# 16-Power.net
KiCad netlist of a schematic drawn in Altium Designer
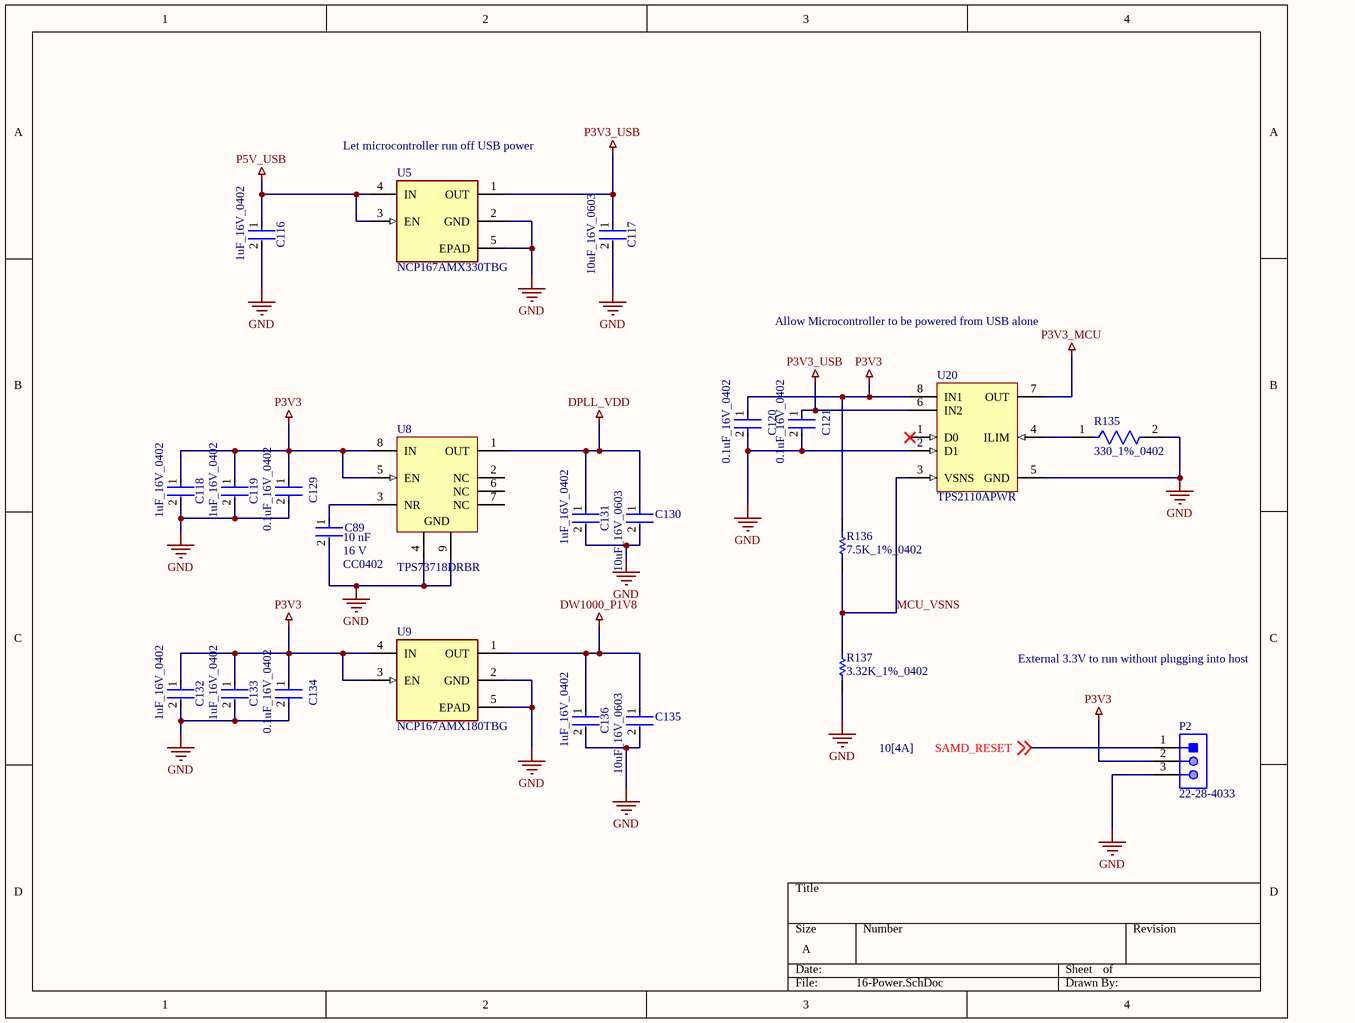
[diagram p0: 16-Power.SchDoc]

(export (version "E")
  (design (tool "Eeschema 10.0.6"))
  (components
    (comp (ref "C89")
      (value "10 nF")
      (footprint "FP-CC0402-MFG")
      (description "CAP CER 10000PF 16V X7R 0402")
      (fields
        (field (name "MANUFACTURER PART NUMBER") "CC0402KRX7R7BB103")
        (field (name "TOLERANCE") "0.1")
        (field (name "PACKAGE") "CC0402")
        (field (name "VOLTAGE RATING") "16 V")
      )
      (libsource (lib "Altium Content Vault") (part "11868f565c42a9108669ba33697ecf6"))
    )
    (comp (ref "C116")
      (value "1uF_16V_0402")
      (footprint "FP-0402-L_1_0_0_05-W_0_5-IPC_C")
      (description "None")
      (fields (field (name "TOLERANCE") "20%") (field (name "VOLTAGE") "16V"))
      (libsource (lib "Altium Content Vault") (part "b4654b650e69147ec39a6b967a45e02"))
    )
    (comp (ref "C117")
      (value "10uF_16V_0603")
      (footprint "FP-C1608-MFG")
      (description "CAP CER 10UF 16V X5R 0603")
      (fields
        (field (name "OCTOPART") "https://octopart.com/c1608x5r1c106m080ab-tdk-26013480")
        (field (name "MANUFACTURER") "TDK Corporation")
      )
      (libsource (lib "Altium Content Vault") (part "11868f565c42a9108669ba33697ecf6"))
    )
    (comp (ref "C118")
      (value "1uF_16V_0402")
      (footprint "FP-0402-L_1_0_0_05-W_0_5-IPC_C")
      (description "None")
      (fields (field (name "TOLERANCE") "20%") (field (name "VOLTAGE") "16V"))
      (libsource (lib "Altium Content Vault") (part "b4654b650e69147ec39a6b967a45e02"))
    )
    (comp (ref "C119")
      (value "1uF_16V_0402")
      (footprint "FP-0402-L_1_0_0_05-W_0_5-IPC_C")
      (description "None")
      (fields (field (name "TOLERANCE") "20%") (field (name "VOLTAGE") "16V"))
      (libsource (lib "Altium Content Vault") (part "b4654b650e69147ec39a6b967a45e02"))
    )
    (comp (ref "C120")
      (value "0.1uF_16V_0402")
      (footprint "FP-GRM15-MFG")
      (description "CAP CER 0.1UF 16V X7R 0402")
      (fields (field (name "MANUFACTURER PART NUMBER") "GRM155R71C104KA88D") (field (name "TOLERANCE") "10%"))
      (libsource (lib "Altium Content Vault") (part "236180d848d6139a670b325ea6854c9"))
    )
    (comp (ref "C121")
      (value "0.1uF_16V_0402")
      (footprint "FP-GRM15-MFG")
      (description "CAP CER 0.1UF 16V X7R 0402")
      (fields (field (name "MANUFACTURER PART NUMBER") "GRM155R71C104KA88D") (field (name "TOLERANCE") "10%"))
      (libsource (lib "Altium Content Vault") (part "236180d848d6139a670b325ea6854c9"))
    )
    (comp (ref "C129")
      (value "0.1uF_16V_0402")
      (footprint "FP-GRM15-MFG")
      (description "CAP CER 0.1UF 16V X7R 0402")
      (fields (field (name "MANUFACTURER PART NUMBER") "GRM155R71C104KA88D") (field (name "TOLERANCE") "10%"))
      (libsource (lib "Altium Content Vault") (part "236180d848d6139a670b325ea6854c9"))
    )
    (comp (ref "C130")
      (value "10uF_16V_0603")
      (footprint "FP-MK107BA-IPC_A")
      (description "None")
      (fields (field (name "TOLERANCE") "20%"))
      (libsource (lib "Altium Content Vault") (part "b4654b650e69147ec39a6b967a45e02"))
    )
    (comp (ref "C131")
      (value "1uF_16V_0402")
      (footprint "FP-0402-L_1_0_0_05-W_0_5-IPC_C")
      (description "None")
      (fields (field (name "TOLERANCE") "20%") (field (name "VOLTAGE") "16V"))
      (libsource (lib "Altium Content Vault") (part "b4654b650e69147ec39a6b967a45e02"))
    )
    (comp (ref "C132")
      (value "1uF_16V_0402")
      (footprint "FP-0402-L_1_0_0_05-W_0_5-IPC_C")
      (description "None")
      (fields (field (name "TOLERANCE") "20%") (field (name "VOLTAGE") "16V"))
      (libsource (lib "Altium Content Vault") (part "b4654b650e69147ec39a6b967a45e02"))
    )
    (comp (ref "C133")
      (value "1uF_16V_0402")
      (footprint "FP-0402-L_1_0_0_05-W_0_5-IPC_C")
      (description "None")
      (fields (field (name "TOLERANCE") "20%") (field (name "VOLTAGE") "16V"))
      (libsource (lib "Altium Content Vault") (part "b4654b650e69147ec39a6b967a45e02"))
    )
    (comp (ref "C134")
      (value "0.1uF_16V_0402")
      (footprint "FP-GRM15-MFG")
      (description "CAP CER 0.1UF 16V X7R 0402")
      (fields (field (name "MANUFACTURER PART NUMBER") "GRM155R71C104KA88D") (field (name "TOLERANCE") "10%"))
      (libsource (lib "Altium Content Vault") (part "236180d848d6139a670b325ea6854c9"))
    )
    (comp (ref "C135")
      (value "10uF_16V_0603")
      (footprint "FP-MK107BA-IPC_A")
      (description "None")
      (fields (field (name "TOLERANCE") "20%"))
      (libsource (lib "Altium Content Vault") (part "b4654b650e69147ec39a6b967a45e02"))
    )
    (comp (ref "C136")
      (value "1uF_16V_0402")
      (footprint "FP-0402-L_1_0_0_05-W_0_5-IPC_C")
      (description "None")
      (fields (field (name "TOLERANCE") "20%") (field (name "VOLTAGE") "16V"))
      (libsource (lib "Altium Content Vault") (part "b4654b650e69147ec39a6b967a45e02"))
    )
    (comp (ref "P2")
      (value "22-28-4033")
      (footprint "MOLX-22-28-4033_V")
      (description "Male Header, Pitch 2.54 mm, 1 x 3 Position, Height 8.38 mm, Tail Length 3.18 mm, RoHS, Bulk")
      (fields (field (name "MANUFACTURER") "Molex"))
      (libsource (lib "Altium Content Vault") (part "CN-1P-M-R3"))
    )
    (comp (ref "R135")
      (value "330_1%_0402")
      (footprint "FP-RC1005-IPC_B")
      (description "Res Thick Film 0402 330Ω 1% 0.063W ±100ppm/°C Molded SMD T/R")
      (fields (field (name "TOLERANCE") "1%"))
      (libsource (lib "Altium Content Vault") (part "1029c3af85768c4190bb7ad29bc67b5"))
    )
    (comp (ref "R136")
      (value "7.5K_1%_0402")
      (footprint "RESC1005X40X25ML05T05")
      (fields (field (name "MANUFACTURER") "Vishay Dale") (field (name "PART NUMBER") "CRCW04027K50FKTD"))
      (libsource (lib "Altium Content Vault") (part "RES"))
    )
    (comp (ref "R137")
      (value "3.32K_1%_0402")
      (footprint "RESC1005X40X25NL05T05")
      (fields (field (name "MANUFACTURER") "Vishay Dale") (field (name "PART NUMBER") "CRCW04023K32FKTD"))
      (libsource (lib "Altium Content Vault") (part "RES"))
    )
    (comp (ref "U5")
      (value "NCP167AMX330TBG")
      (footprint "FP-711AJ-MFG")
      (description "LDO 700 MA ULTRA-LOW NOI")
      (fields
        (field (name "OCTOPART") "https://octopart.com/ncp167amx330tbg-on+semiconductor-85869721")
        (field (name "MANUFACTURER") "ON Semiconductor")
      )
      (libsource (lib "Altium Content Vault") (part "8b0df6fa3425eee82d30c7ddf45be47"))
    )
    (comp (ref "U8")
      (value "TPS73718DRBR")
      (footprint "DRB0008A_V")
      (fields (field (name "MANUFACTURER") "Texas Instruments"))
      (libsource (lib "Altium Content Vault") (part "TI-TPS73718DRB8-1750X1500TP"))
    )
    (comp (ref "U9")
      (value "NCP167AMX180TBG")
      (footprint "FP-711AJ-MFG")
      (description "LDO 700 MA ULTRA-LOW NOI")
      (fields
        (field (name "OCTOPART") "https://octopart.com/ncp167amx330tbg-on+semiconductor-85869721")
        (field (name "MANUFACTURER") "ON Semiconductor")
      )
      (libsource (lib "Altium Content Vault") (part "8b0df6fa3425eee82d30c7ddf45be47"))
    )
    (comp (ref "U20")
      (value "TPS2110APWR")
      (footprint "PW0008A_L")
      (fields (field (name "MANUFACTURER") "Texas Instruments"))
      (libsource (lib "Altium Content Vault") (part "TI-TPS2110APW8"))
    )
  )
  (nets
    (net (code "1") (name "/MCU_VSNS") (class "Default")
      (node (ref "R136") (pin "1") (pinfunction "1_1") (pintype "passive"))
      (node (ref "R137") (pin "2") (pinfunction "2_2") (pintype "passive"))
      (node (ref "U20") (pin "3") (pinfunction "VSNS_3") (pintype "input"))
    )
    (net (code "2") (name "DPLL_VDD") (class "Default")
      (node (ref "C130") (pin "1") (pinfunction "1_1") (pintype "passive"))
      (node (ref "C131") (pin "1") (pinfunction "1_1") (pintype "passive"))
      (node (ref "U8") (pin "1") (pinfunction "OUT_1") (pintype "power_in"))
    )
    (net (code "3") (name "DW1000_P1V8") (class "Default")
      (node (ref "C135") (pin "1") (pinfunction "1_1") (pintype "passive"))
      (node (ref "C136") (pin "1") (pinfunction "1_1") (pintype "passive"))
      (node (ref "U9") (pin "1") (pinfunction "OUT_1") (pintype "power_in"))
    )
    (net (code "4") (name "GND") (class "Default")
      (node (ref "C116") (pin "2") (pinfunction "2_2") (pintype "passive"))
      (node (ref "C117") (pin "2") (pinfunction "2_2") (pintype "passive"))
      (node (ref "C118") (pin "2") (pinfunction "2_2") (pintype "passive"))
      (node (ref "C119") (pin "2") (pinfunction "2_2") (pintype "passive"))
      (node (ref "C120") (pin "2") (pinfunction "2_2") (pintype "passive"))
      (node (ref "C121") (pin "2") (pinfunction "2_2") (pintype "passive"))
      (node (ref "C129") (pin "2") (pinfunction "2_2") (pintype "passive"))
      (node (ref "C130") (pin "2") (pinfunction "2_2") (pintype "passive"))
      (node (ref "C131") (pin "2") (pinfunction "2_2") (pintype "passive"))
      (node (ref "C132") (pin "2") (pinfunction "2_2") (pintype "passive"))
      (node (ref "C133") (pin "2") (pinfunction "2_2") (pintype "passive"))
      (node (ref "C134") (pin "2") (pinfunction "2_2") (pintype "passive"))
      (node (ref "C135") (pin "2") (pinfunction "2_2") (pintype "passive"))
      (node (ref "C136") (pin "2") (pinfunction "2_2") (pintype "passive"))
      (node (ref "C89") (pin "2") (pinfunction "2_2") (pintype "passive"))
      (node (ref "P2") (pin "3") (pinfunction "3_3") (pintype "passive"))
      (node (ref "R135") (pin "2") (pinfunction "2_2") (pintype "passive"))
      (node (ref "R137") (pin "1") (pinfunction "1_1") (pintype "passive"))
      (node (ref "U20") (pin "2") (pinfunction "D1_2") (pintype "input"))
      (node (ref "U20") (pin "5") (pinfunction "GND_5") (pintype "power_in"))
      (node (ref "U5") (pin "2") (pinfunction "GND_2") (pintype "power_in"))
      (node (ref "U5") (pin "5") (pinfunction "EPAD_5") (pintype "power_in"))
      (node (ref "U8") (pin "4") (pinfunction "GND_4") (pintype "power_in"))
      (node (ref "U8") (pin "9") (pinfunction "GND_9") (pintype "power_in"))
      (node (ref "U9") (pin "2") (pinfunction "GND_2") (pintype "power_in"))
      (node (ref "U9") (pin "5") (pinfunction "EPAD_5") (pintype "power_in"))
    )
    (net (code "5") (name "Net-(U8-NR)") (class "Default")
      (node (ref "C89") (pin "1") (pinfunction "1_1") (pintype "passive"))
      (node (ref "U8") (pin "3") (pinfunction "NR_3") (pintype "passive"))
    )
    (net (code "6") (name "Net-(U20-ILIM)") (class "Default")
      (node (ref "R135") (pin "1") (pinfunction "1_1") (pintype "passive"))
      (node (ref "U20") (pin "4") (pinfunction "ILIM_4") (pintype "input"))
    )
    (net (code "7") (name "P3V3") (class "Default")
      (node (ref "C118") (pin "1") (pinfunction "1_1") (pintype "passive"))
      (node (ref "C119") (pin "1") (pinfunction "1_1") (pintype "passive"))
      (node (ref "C120") (pin "1") (pinfunction "1_1") (pintype "passive"))
      (node (ref "C129") (pin "1") (pinfunction "1_1") (pintype "passive"))
      (node (ref "C132") (pin "1") (pinfunction "1_1") (pintype "passive"))
      (node (ref "C133") (pin "1") (pinfunction "1_1") (pintype "passive"))
      (node (ref "C134") (pin "1") (pinfunction "1_1") (pintype "passive"))
      (node (ref "P2") (pin "2") (pinfunction "2_2") (pintype "passive"))
      (node (ref "R136") (pin "2") (pinfunction "2_2") (pintype "passive"))
      (node (ref "U20") (pin "8") (pinfunction "IN1_8") (pintype "power_in"))
      (node (ref "U8") (pin "5") (pinfunction "EN_5") (pintype "input"))
      (node (ref "U8") (pin "8") (pinfunction "IN_8") (pintype "power_in"))
      (node (ref "U9") (pin "3") (pinfunction "EN_3") (pintype "input"))
      (node (ref "U9") (pin "4") (pinfunction "IN_4") (pintype "power_in"))
    )
    (net (code "8") (name "P3V3_MCU") (class "Default")
      (node (ref "U20") (pin "7") (pinfunction "OUT_7") (pintype "power_in"))
    )
    (net (code "9") (name "P3V3_USB") (class "Default")
      (node (ref "C117") (pin "1") (pinfunction "1_1") (pintype "passive"))
      (node (ref "C121") (pin "1") (pinfunction "1_1") (pintype "passive"))
      (node (ref "U20") (pin "6") (pinfunction "IN2_6") (pintype "power_in"))
      (node (ref "U5") (pin "1") (pinfunction "OUT_1") (pintype "power_in"))
    )
    (net (code "10") (name "P5V_USB") (class "Default")
      (node (ref "C116") (pin "1") (pinfunction "1_1") (pintype "passive"))
      (node (ref "U5") (pin "3") (pinfunction "EN_3") (pintype "input"))
      (node (ref "U5") (pin "4") (pinfunction "IN_4") (pintype "power_in"))
    )
    (net (code "11") (name "SAMD_RESET") (class "Default")
      (node (ref "P2") (pin "1") (pinfunction "1_1") (pintype "passive"))
    )
    (net (code "12") (name "unconnected-(U8-NC-Pad2)") (class "Default")
      (node (ref "U8") (pin "2") (pinfunction "NC_2") (pintype "passive"))
    )
    (net (code "13") (name "unconnected-(U8-NC-Pad6)") (class "Default")
      (node (ref "U8") (pin "6") (pinfunction "NC_6") (pintype "passive"))
    )
    (net (code "14") (name "unconnected-(U8-NC-Pad7)") (class "Default")
      (node (ref "U8") (pin "7") (pinfunction "NC_7") (pintype "passive"))
    )
    (net (code "15") (name "unconnected-(U20-D0-Pad1)") (class "Default")
      (node (ref "U20") (pin "1") (pinfunction "D0_1") (pintype "input+no_connect"))
    )
  )
)
